# HAT-MAGIC-HOOVER-BASE.net
KiCad netlist of a schematic drawn in EasyEDA
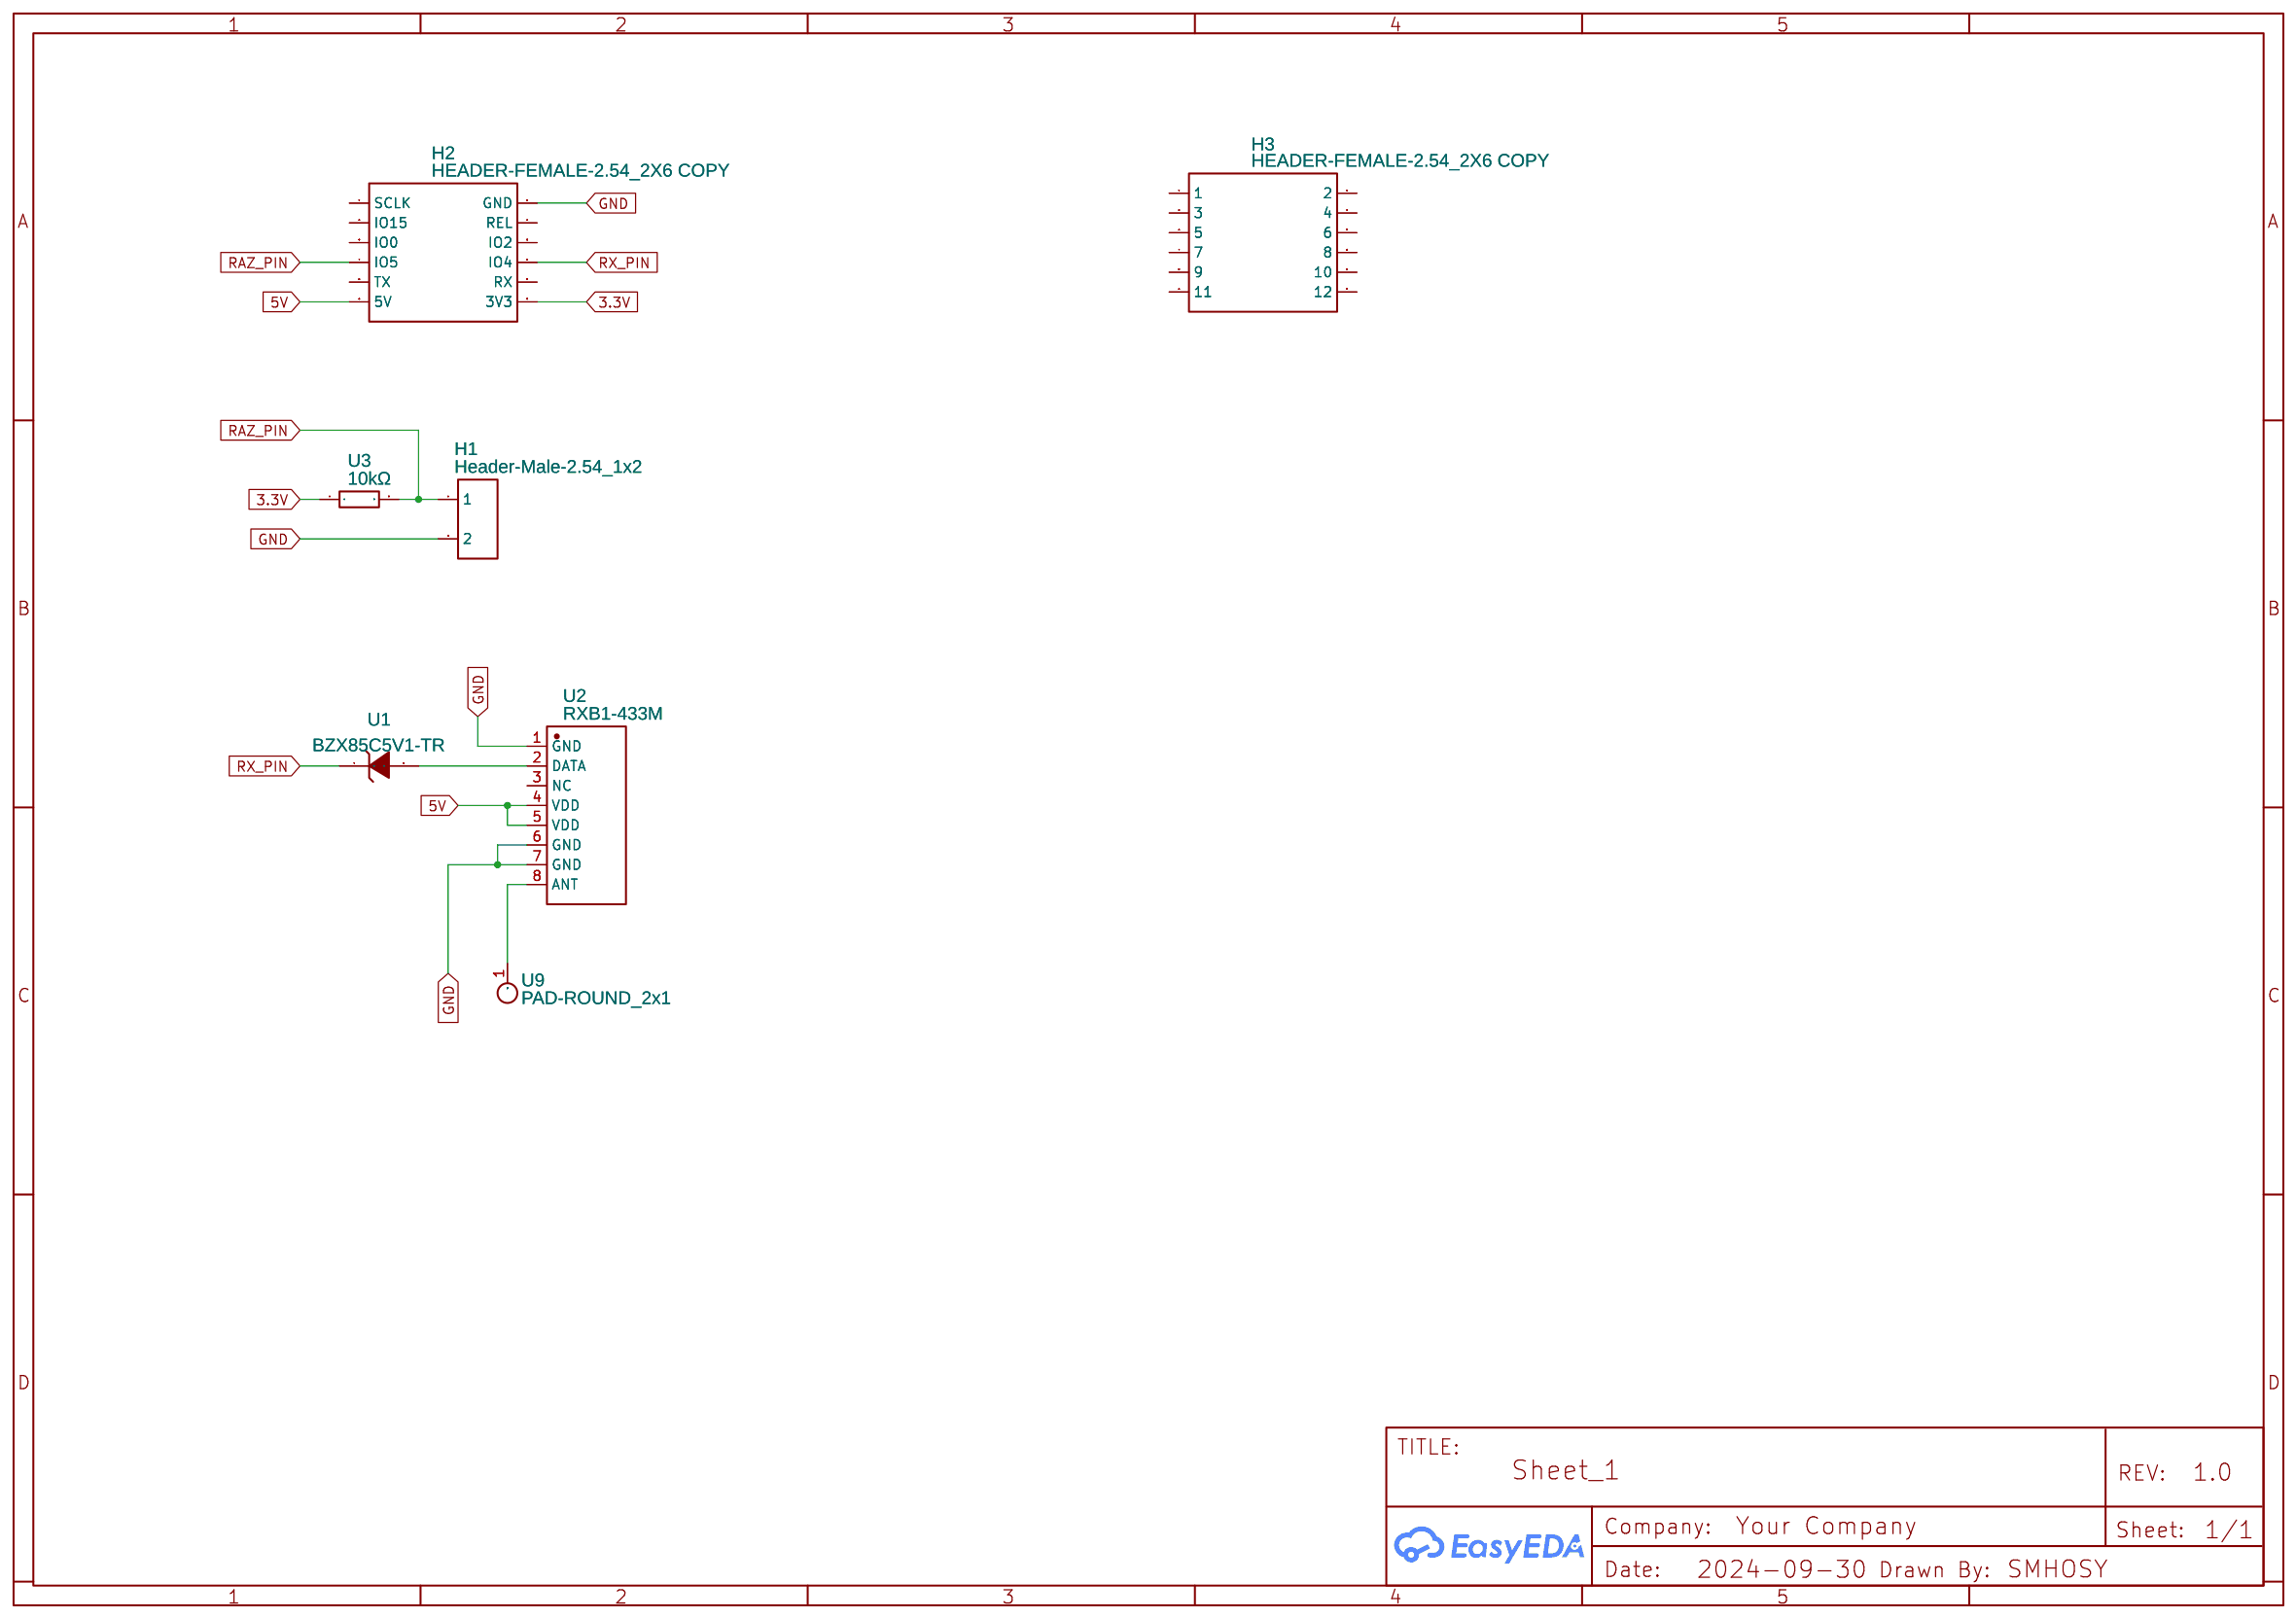
[diagram p0: schematic sheet]

(export (version "E")
  (design (tool "Eeschema 10.0.6"))
  (components
    (comp (ref "H1")
      (value "Header-Male-2.54_1x2")
      (fields
        (field (name "Manufacturer Part") "826629-2")
        (field (name "Manufacturer") "TE Connectivity(泰科电子)")
      )
      (libsource (lib "") (part "Header-Male-2.54_1x2"))
    )
    (comp (ref "H2")
      (value "HEADER-FEMALE-2.54_2X6 COPY")
      (fields (field (name "Manufacturer Part") "2.54-2*6P母") (field (name "Manufacturer") "BOOMELE(博穆精密)"))
      (libsource (lib "") (part "HEADER-FEMALE-2.54_2X6 COPY"))
    )
    (comp (ref "H3")
      (value "HEADER-FEMALE-2.54_2X6 COPY")
      (fields (field (name "Manufacturer Part") "2.54-2*6P母") (field (name "Manufacturer") "BOOMELE(博穆精密)"))
      (libsource (lib "") (part "HEADER-FEMALE-2.54_2X6 COPY_1"))
    )
    (comp (ref "U1")
      (value "BZX85C5V1-TR")
      (fields (field (name "Manufacturer") "VISHAY(威世)"))
      (libsource (lib "") (part "BZX85C5V1-TR"))
    )
    (comp (ref "U2")
      (value "RXB1-433M")
      (fields (field (name "Manufacturer") "DreamLNK(骏晔科技)"))
      (libsource (lib "") (part "RXB1-433M"))
    )
    (comp (ref "U3")
      (value "10kΩ")
      (fields
        (field (name "Manufacturer Part") "HR1206J10K0P05Z")
        (field (name "Manufacturer") "EVER OHMS(天二科技)")
      )
      (libsource (lib "") (part "HR1206J10KP05"))
    )
    (comp (ref "U9") (value "PAD-ROUND_2x1") (libsource (lib "") (part "PAD-ROUND_2x1")))
  )
  (nets
    (net (code "1") (name "3.3V") (class "Default")
      (node (ref "H2") (pin "12") (pinfunction "3V3_12") (pintype "input"))
      (node (ref "U3") (pin "1") (pinfunction "1_1") (pintype "unspecified"))
    )
    (net (code "2") (name "5V") (class "Default")
      (node (ref "H2") (pin "11") (pinfunction "5V_11") (pintype "input"))
      (node (ref "U2") (pin "4") (pinfunction "VDD_4") (pintype "unspecified"))
      (node (ref "U2") (pin "5") (pinfunction "VDD_5") (pintype "unspecified"))
    )
    (net (code "3") (name "GND") (class "Default")
      (node (ref "H1") (pin "2") (pinfunction "2_2") (pintype "unspecified"))
      (node (ref "H2") (pin "2") (pinfunction "GND_2") (pintype "input"))
      (node (ref "U2") (pin "1") (pinfunction "GND_1") (pintype "unspecified"))
      (node (ref "U2") (pin "6") (pinfunction "GND_6") (pintype "unspecified"))
      (node (ref "U2") (pin "7") (pinfunction "GND_7") (pintype "unspecified"))
    )
    (net (code "4") (name "Net-(U1-A)") (class "Default")
      (node (ref "U1") (pin "2") (pinfunction "A_2") (pintype "unspecified"))
      (node (ref "U2") (pin "2") (pinfunction "DATA_2") (pintype "unspecified"))
    )
    (net (code "5") (name "Net-(U2-ANT)") (class "Default")
      (node (ref "U2") (pin "8") (pinfunction "ANT_8") (pintype "unspecified"))
      (node (ref "U9") (pin "1") (pinfunction "Pad_1") (pintype "unspecified"))
    )
    (net (code "6") (name "RAZ_PIN") (class "Default")
      (node (ref "H1") (pin "1") (pinfunction "1_1") (pintype "unspecified"))
      (node (ref "H2") (pin "7") (pinfunction "IO5_7") (pintype "input"))
      (node (ref "U3") (pin "2") (pinfunction "2_2") (pintype "unspecified"))
    )
    (net (code "7") (name "RX_PIN") (class "Default")
      (node (ref "H2") (pin "8") (pinfunction "IO4_8") (pintype "input"))
      (node (ref "U1") (pin "1") (pinfunction "C_1") (pintype "unspecified"))
    )
    (net (code "8") (name "unconnected-(H2-IO0-Pad5)") (class "Default")
      (node (ref "H2") (pin "5") (pinfunction "IO0_5") (pintype "input"))
    )
    (net (code "9") (name "unconnected-(H2-IO2-Pad6)") (class "Default")
      (node (ref "H2") (pin "6") (pinfunction "IO2_6") (pintype "input"))
    )
    (net (code "10") (name "unconnected-(H2-IO15-Pad3)") (class "Default")
      (node (ref "H2") (pin "3") (pinfunction "IO15_3") (pintype "input"))
    )
    (net (code "11") (name "unconnected-(H2-REL-Pad4)") (class "Default")
      (node (ref "H2") (pin "4") (pinfunction "REL_4") (pintype "input"))
    )
    (net (code "12") (name "unconnected-(H2-RX-Pad10)") (class "Default")
      (node (ref "H2") (pin "10") (pinfunction "RX_10") (pintype "input"))
    )
    (net (code "13") (name "unconnected-(H2-SCLK-Pad1)") (class "Default")
      (node (ref "H2") (pin "1") (pinfunction "SCLK_1") (pintype "input"))
    )
    (net (code "14") (name "unconnected-(H2-TX-Pad9)") (class "Default")
      (node (ref "H2") (pin "9") (pinfunction "TX_9") (pintype "input"))
    )
    (net (code "15") (name "unconnected-(H3-Pad1)") (class "Default")
      (node (ref "H3") (pin "1") (pinfunction "1_1") (pintype "input"))
    )
    (net (code "16") (name "unconnected-(H3-Pad2)") (class "Default")
      (node (ref "H3") (pin "2") (pinfunction "2_2") (pintype "input"))
    )
    (net (code "17") (name "unconnected-(H3-Pad3)") (class "Default")
      (node (ref "H3") (pin "3") (pinfunction "3_3") (pintype "input"))
    )
    (net (code "18") (name "unconnected-(H3-Pad4)") (class "Default")
      (node (ref "H3") (pin "4") (pinfunction "4_4") (pintype "input"))
    )
    (net (code "19") (name "unconnected-(H3-Pad5)") (class "Default")
      (node (ref "H3") (pin "5") (pinfunction "5_5") (pintype "input"))
    )
    (net (code "20") (name "unconnected-(H3-Pad6)") (class "Default")
      (node (ref "H3") (pin "6") (pinfunction "6_6") (pintype "input"))
    )
    (net (code "21") (name "unconnected-(H3-Pad7)") (class "Default")
      (node (ref "H3") (pin "7") (pinfunction "7_7") (pintype "input"))
    )
    (net (code "22") (name "unconnected-(H3-Pad8)") (class "Default")
      (node (ref "H3") (pin "8") (pinfunction "8_8") (pintype "input"))
    )
    (net (code "23") (name "unconnected-(H3-Pad9)") (class "Default")
      (node (ref "H3") (pin "9") (pinfunction "9_9") (pintype "input"))
    )
    (net (code "24") (name "unconnected-(H3-Pad10)") (class "Default")
      (node (ref "H3") (pin "10") (pinfunction "10_10") (pintype "input"))
    )
    (net (code "25") (name "unconnected-(H3-Pad11)") (class "Default")
      (node (ref "H3") (pin "11") (pinfunction "11_11") (pintype "input"))
    )
    (net (code "26") (name "unconnected-(H3-Pad12)") (class "Default")
      (node (ref "H3") (pin "12") (pinfunction "12_12") (pintype "input"))
    )
    (net (code "27") (name "unconnected-(U2-NC-Pad3)") (class "Default")
      (node (ref "U2") (pin "3") (pinfunction "NC_3") (pintype "unspecified"))
    )
  )
)
